# Motor_driver.net
KiCad netlist of a schematic drawn in Altium Designer
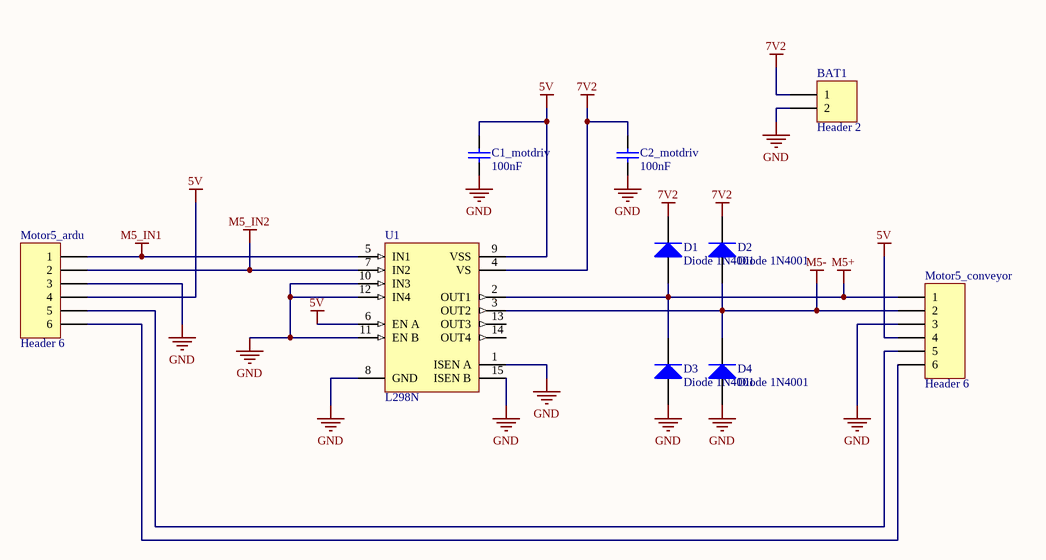
[diagram p0: Motor_driver.SchDoc]

(export (version "E")
  (design (tool "Eeschema 10.0.6"))
  (components
    (comp (ref "BAT1")
      (value "Header 2")
      (footprint "STL1550/2-3.5")
      (description "Header, 2-Pin")
      (fields (field (name "PUBLISHER") "Altium Limited"))
      (libsource (lib "Miscellaneous Connectors") (part "Header 2"))
    )
    (comp (ref "C1_motdriv")
      (value "100nF")
      (footprint "CAPC1608N")
      (description "Capacitor")
      (fields (field (name "PUBLISHER") "Altium Limited"))
      (libsource (lib "Miscellaneous Devices") (part "Cap"))
    )
    (comp (ref "C2_motdriv")
      (value "100nF")
      (footprint "CAPC1608N")
      (description "Capacitor")
      (fields (field (name "PUBLISHER") "Altium Limited"))
      (libsource (lib "Miscellaneous Devices") (part "Cap"))
    )
    (comp (ref "D1")
      (value "Diode 1N4001")
      (footprint "DO-41")
      (description "1 Amp General Purpose Rectifier")
      (fields (field (name "PUBLISHER") "Altium Limited"))
      (libsource (lib "Miscellaneous Devices") (part "Diode 1N4001"))
    )
    (comp (ref "D2")
      (value "Diode 1N4001")
      (footprint "DO-41")
      (description "1 Amp General Purpose Rectifier")
      (fields (field (name "PUBLISHER") "Altium Limited"))
      (libsource (lib "Miscellaneous Devices") (part "Diode 1N4001"))
    )
    (comp (ref "D3")
      (value "Diode 1N4001")
      (footprint "DO-41")
      (description "1 Amp General Purpose Rectifier")
      (fields (field (name "PUBLISHER") "Altium Limited"))
      (libsource (lib "Miscellaneous Devices") (part "Diode 1N4001"))
    )
    (comp (ref "D4")
      (value "Diode 1N4001")
      (footprint "DO-41")
      (description "1 Amp General Purpose Rectifier")
      (fields (field (name "PUBLISHER") "Altium Limited"))
      (libsource (lib "Miscellaneous Devices") (part "Diode 1N4001"))
    )
    (comp (ref "Motor5_ardu")
      (value "Header 6")
      (footprint "HDR1X6")
      (description "Header, 6-Pin")
      (fields (field (name "PUBLISHER") "Altium Limited"))
      (libsource (lib "Miscellaneous Connectors") (part "Header 6"))
    )
    (comp (ref "Motor5_conveyor")
      (value "Header 6")
      (footprint "HDR1X6")
      (description "Header, 6-Pin")
      (fields (field (name "PUBLISHER") "Altium Limited"))
      (libsource (lib "") (part "Header 6_1"))
    )
    (comp (ref "U1")
      (value "L298N")
      (footprint "MULTIWAT15")
      (description "Dual Full Bridge Driver")
      (fields (field (name "PUBLISHER") "Altium Limited"))
      (libsource (lib "ST Interface DC Motor Controller") (part "L298N"))
    )
  )
  (nets
    (net (code "1") (name "5V") (class "Default")
      (node (ref "C1_motdriv") (pin "2") (pinfunction "2_2") (pintype "passive"))
      (node (ref "Motor5_ardu") (pin "4") (pinfunction "4_4") (pintype "passive"))
      (node (ref "Motor5_conveyor") (pin "4") (pinfunction "4_4") (pintype "passive"))
      (node (ref "U1") (pin "6") (pinfunction "EN_A_6") (pintype "input"))
      (node (ref "U1") (pin "9") (pinfunction "VSS_9") (pintype "power_in"))
    )
    (net (code "2") (name "7V2") (class "Default")
      (node (ref "BAT1") (pin "1") (pinfunction "1_1") (pintype "passive"))
      (node (ref "C2_motdriv") (pin "2") (pinfunction "2_2") (pintype "passive"))
      (node (ref "D1") (pin "2") (pinfunction "K_2") (pintype "passive"))
      (node (ref "D2") (pin "2") (pinfunction "K_2") (pintype "passive"))
      (node (ref "U1") (pin "4") (pinfunction "VS_4") (pintype "power_in"))
    )
    (net (code "3") (name "GND") (class "Default")
      (node (ref "BAT1") (pin "2") (pinfunction "2_2") (pintype "passive"))
      (node (ref "C1_motdriv") (pin "1") (pinfunction "1_1") (pintype "passive"))
      (node (ref "C2_motdriv") (pin "1") (pinfunction "1_1") (pintype "passive"))
      (node (ref "D3") (pin "1") (pinfunction "A_1") (pintype "passive"))
      (node (ref "D4") (pin "1") (pinfunction "A_1") (pintype "passive"))
      (node (ref "Motor5_ardu") (pin "3") (pinfunction "3_3") (pintype "passive"))
      (node (ref "Motor5_conveyor") (pin "3") (pinfunction "3_3") (pintype "passive"))
      (node (ref "U1") (pin "1") (pinfunction "ISEN_A_1") (pintype "passive"))
      (node (ref "U1") (pin "10") (pinfunction "IN3_10") (pintype "input"))
      (node (ref "U1") (pin "11") (pinfunction "EN_B_11") (pintype "input"))
      (node (ref "U1") (pin "12") (pinfunction "IN4_12") (pintype "input"))
      (node (ref "U1") (pin "15") (pinfunction "ISEN_B_15") (pintype "passive"))
      (node (ref "U1") (pin "8") (pinfunction "GND_8") (pintype "power_in"))
    )
    (net (code "4") (name "M5+") (class "Default")
      (node (ref "D1") (pin "1") (pinfunction "A_1") (pintype "passive"))
      (node (ref "D3") (pin "2") (pinfunction "K_2") (pintype "passive"))
      (node (ref "Motor5_conveyor") (pin "1") (pinfunction "1_1") (pintype "passive"))
      (node (ref "U1") (pin "2") (pinfunction "OUT1_2") (pintype "output"))
    )
    (net (code "5") (name "M5-") (class "Default")
      (node (ref "D2") (pin "1") (pinfunction "A_1") (pintype "passive"))
      (node (ref "D4") (pin "2") (pinfunction "K_2") (pintype "passive"))
      (node (ref "Motor5_conveyor") (pin "2") (pinfunction "2_2") (pintype "passive"))
      (node (ref "U1") (pin "3") (pinfunction "OUT2_3") (pintype "output"))
    )
    (net (code "6") (name "M5_IN1") (class "Default")
      (node (ref "Motor5_ardu") (pin "1") (pinfunction "1_1") (pintype "passive"))
      (node (ref "U1") (pin "5") (pinfunction "IN1_5") (pintype "input"))
    )
    (net (code "7") (name "M5_IN2") (class "Default")
      (node (ref "Motor5_ardu") (pin "2") (pinfunction "2_2") (pintype "passive"))
      (node (ref "U1") (pin "7") (pinfunction "IN2_7") (pintype "input"))
    )
    (net (code "8") (name "Net-(Motor5_ardu-Pad5)") (class "Default")
      (node (ref "Motor5_ardu") (pin "5") (pinfunction "5_5") (pintype "passive"))
      (node (ref "Motor5_conveyor") (pin "5") (pinfunction "5_5") (pintype "passive"))
    )
    (net (code "9") (name "Net-(Motor5_ardu-Pad6)") (class "Default")
      (node (ref "Motor5_ardu") (pin "6") (pinfunction "6_6") (pintype "passive"))
      (node (ref "Motor5_conveyor") (pin "6") (pinfunction "6_6") (pintype "passive"))
    )
    (net (code "10") (name "unconnected-(U1-OUT3-Pad13)") (class "Default")
      (node (ref "U1") (pin "13") (pinfunction "OUT3_13") (pintype "output"))
    )
    (net (code "11") (name "unconnected-(U1-OUT4-Pad14)") (class "Default")
      (node (ref "U1") (pin "14") (pinfunction "OUT4_14") (pintype "output"))
    )
  )
)
